# primary_cap_board_4s2p.net
KiCad netlist of a schematic drawn in EAGLE
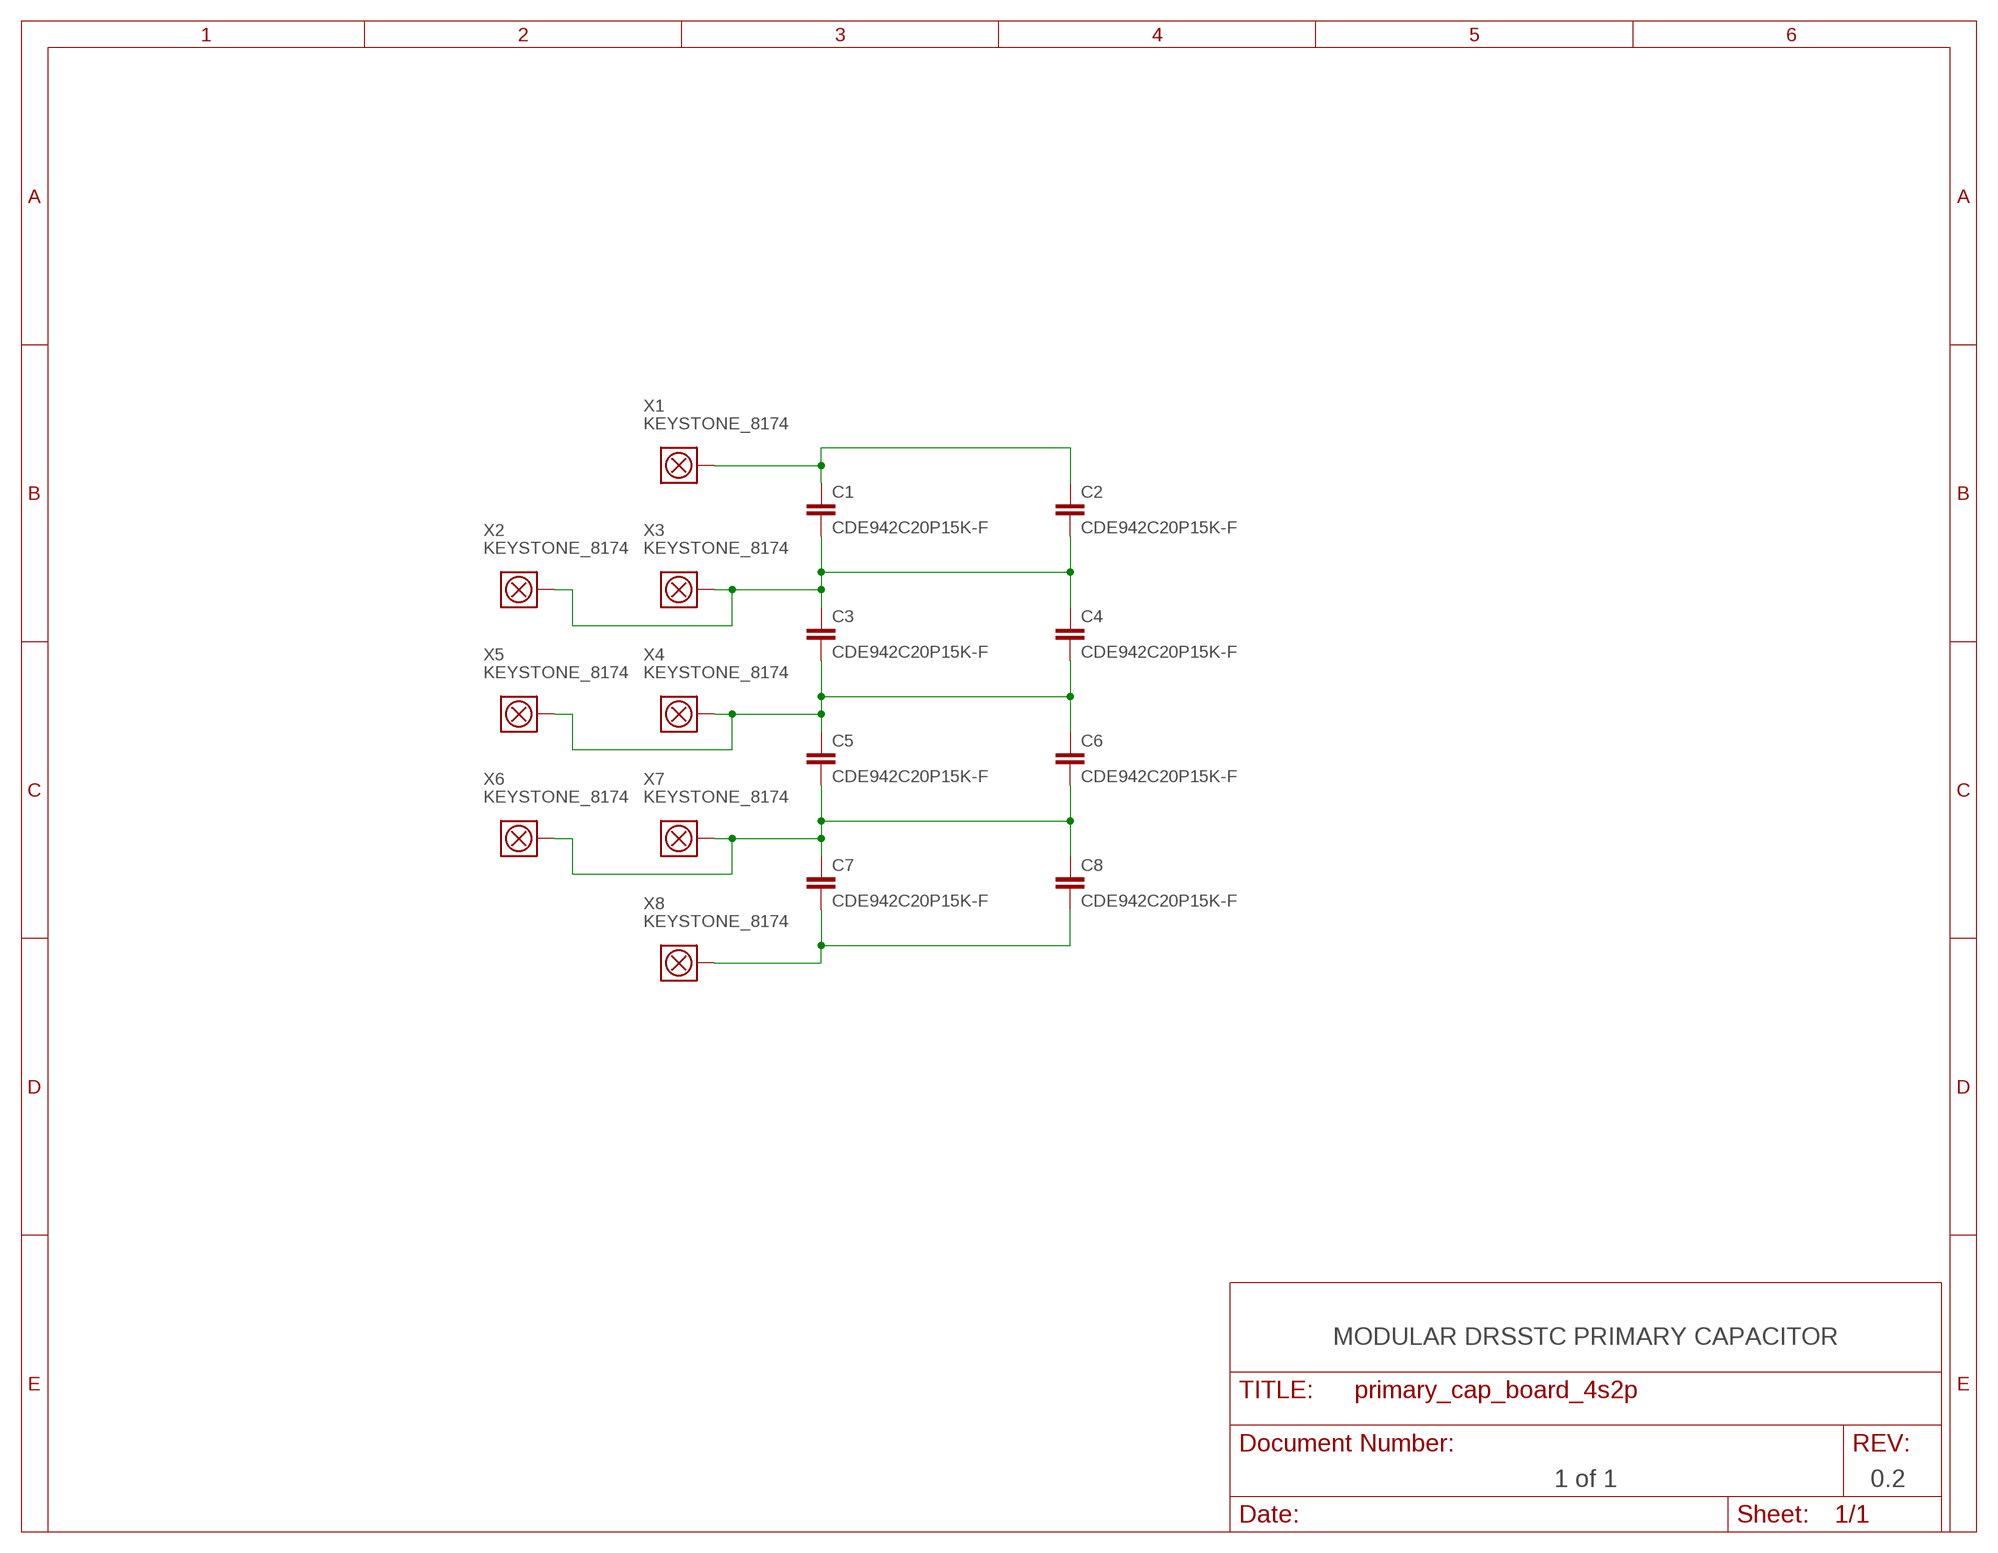
[diagram p0: schematic, sheet 1]

(export (version "E")
  (design (tool "Eeschema 10.0.6"))
  (components
    (comp (ref "C1")
      (value "CDE942C20P15K-F")
      (footprint "eagle-import:CDE942")
      (libsource (lib "eagle-import") (part "CDE942C20P15K-F"))
    )
    (comp (ref "C2")
      (value "CDE942C20P15K-F")
      (footprint "eagle-import:CDE942")
      (libsource (lib "eagle-import") (part "CDE942C20P15K-F"))
    )
    (comp (ref "C3")
      (value "CDE942C20P15K-F")
      (footprint "eagle-import:CDE942")
      (libsource (lib "eagle-import") (part "CDE942C20P15K-F"))
    )
    (comp (ref "C4")
      (value "CDE942C20P15K-F")
      (footprint "eagle-import:CDE942")
      (libsource (lib "eagle-import") (part "CDE942C20P15K-F"))
    )
    (comp (ref "C5")
      (value "CDE942C20P15K-F")
      (footprint "eagle-import:CDE942")
      (libsource (lib "eagle-import") (part "CDE942C20P15K-F"))
    )
    (comp (ref "C6")
      (value "CDE942C20P15K-F")
      (footprint "eagle-import:CDE942")
      (libsource (lib "eagle-import") (part "CDE942C20P15K-F"))
    )
    (comp (ref "C7")
      (value "CDE942C20P15K-F")
      (footprint "eagle-import:CDE942")
      (libsource (lib "eagle-import") (part "CDE942C20P15K-F"))
    )
    (comp (ref "C8")
      (value "CDE942C20P15K-F")
      (footprint "eagle-import:CDE942")
      (libsource (lib "eagle-import") (part "CDE942C20P15K-F"))
    )
    (comp (ref "X1")
      (value "KEYSTONE_8174")
      (footprint "eagle-import:CON_KEYSTONE_8174")
      (libsource (lib "eagle-import") (part "CON_KEYSTONE_8174"))
    )
    (comp (ref "X2")
      (value "KEYSTONE_8174")
      (footprint "eagle-import:CON_KEYSTONE_8174")
      (libsource (lib "eagle-import") (part "CON_KEYSTONE_8174"))
    )
    (comp (ref "X3")
      (value "KEYSTONE_8174")
      (footprint "eagle-import:CON_KEYSTONE_8174")
      (libsource (lib "eagle-import") (part "CON_KEYSTONE_8174"))
    )
    (comp (ref "X4")
      (value "KEYSTONE_8174")
      (footprint "eagle-import:CON_KEYSTONE_8174")
      (libsource (lib "eagle-import") (part "CON_KEYSTONE_8174"))
    )
    (comp (ref "X5")
      (value "KEYSTONE_8174")
      (footprint "eagle-import:CON_KEYSTONE_8174")
      (libsource (lib "eagle-import") (part "CON_KEYSTONE_8174"))
    )
    (comp (ref "X6")
      (value "KEYSTONE_8174")
      (footprint "eagle-import:CON_KEYSTONE_8174")
      (libsource (lib "eagle-import") (part "CON_KEYSTONE_8174"))
    )
    (comp (ref "X7")
      (value "KEYSTONE_8174")
      (footprint "eagle-import:CON_KEYSTONE_8174")
      (libsource (lib "eagle-import") (part "CON_KEYSTONE_8174"))
    )
    (comp (ref "X8")
      (value "KEYSTONE_8174")
      (footprint "eagle-import:CON_KEYSTONE_8174")
      (libsource (lib "eagle-import") (part "CON_KEYSTONE_8174"))
    )
  )
  (nets
    (net (code "1") (name "Net-(C1-1)") (class "Default")
      (node (ref "C1") (pin "P$1") (pinfunction "1_P$1") (pintype "passive"))
      (node (ref "C2") (pin "P$1") (pinfunction "1_P$1") (pintype "passive"))
      (node (ref "X1") (pin "P$1") (pinfunction "PIN1_P$1") (pintype "bidirectional"))
      (node (ref "X1") (pin "P$2") (pinfunction "PIN1_P$2") (pintype "bidirectional"))
      (node (ref "X1") (pin "P$3") (pinfunction "PIN1_P$3") (pintype "bidirectional"))
      (node (ref "X1") (pin "P$4") (pinfunction "PIN1_P$4") (pintype "bidirectional"))
    )
    (net (code "2") (name "Net-(C1-2)") (class "Default")
      (node (ref "C1") (pin "P$2") (pinfunction "2_P$2") (pintype "passive"))
      (node (ref "C2") (pin "P$2") (pinfunction "2_P$2") (pintype "passive"))
      (node (ref "C3") (pin "P$1") (pinfunction "1_P$1") (pintype "passive"))
      (node (ref "C4") (pin "P$1") (pinfunction "1_P$1") (pintype "passive"))
      (node (ref "X2") (pin "P$1") (pinfunction "PIN1_P$1") (pintype "bidirectional"))
      (node (ref "X2") (pin "P$2") (pinfunction "PIN1_P$2") (pintype "bidirectional"))
      (node (ref "X2") (pin "P$3") (pinfunction "PIN1_P$3") (pintype "bidirectional"))
      (node (ref "X2") (pin "P$4") (pinfunction "PIN1_P$4") (pintype "bidirectional"))
      (node (ref "X3") (pin "P$1") (pinfunction "PIN1_P$1") (pintype "bidirectional"))
      (node (ref "X3") (pin "P$2") (pinfunction "PIN1_P$2") (pintype "bidirectional"))
      (node (ref "X3") (pin "P$3") (pinfunction "PIN1_P$3") (pintype "bidirectional"))
      (node (ref "X3") (pin "P$4") (pinfunction "PIN1_P$4") (pintype "bidirectional"))
    )
    (net (code "3") (name "Net-(C3-2)") (class "Default")
      (node (ref "C3") (pin "P$2") (pinfunction "2_P$2") (pintype "passive"))
      (node (ref "C4") (pin "P$2") (pinfunction "2_P$2") (pintype "passive"))
      (node (ref "C5") (pin "P$1") (pinfunction "1_P$1") (pintype "passive"))
      (node (ref "C6") (pin "P$1") (pinfunction "1_P$1") (pintype "passive"))
      (node (ref "X4") (pin "P$1") (pinfunction "PIN1_P$1") (pintype "bidirectional"))
      (node (ref "X4") (pin "P$2") (pinfunction "PIN1_P$2") (pintype "bidirectional"))
      (node (ref "X4") (pin "P$3") (pinfunction "PIN1_P$3") (pintype "bidirectional"))
      (node (ref "X4") (pin "P$4") (pinfunction "PIN1_P$4") (pintype "bidirectional"))
      (node (ref "X5") (pin "P$1") (pinfunction "PIN1_P$1") (pintype "bidirectional"))
      (node (ref "X5") (pin "P$2") (pinfunction "PIN1_P$2") (pintype "bidirectional"))
      (node (ref "X5") (pin "P$3") (pinfunction "PIN1_P$3") (pintype "bidirectional"))
      (node (ref "X5") (pin "P$4") (pinfunction "PIN1_P$4") (pintype "bidirectional"))
    )
    (net (code "4") (name "Net-(C5-2)") (class "Default")
      (node (ref "C5") (pin "P$2") (pinfunction "2_P$2") (pintype "passive"))
      (node (ref "C6") (pin "P$2") (pinfunction "2_P$2") (pintype "passive"))
      (node (ref "C7") (pin "P$1") (pinfunction "1_P$1") (pintype "passive"))
      (node (ref "C8") (pin "P$1") (pinfunction "1_P$1") (pintype "passive"))
      (node (ref "X6") (pin "P$1") (pinfunction "PIN1_P$1") (pintype "bidirectional"))
      (node (ref "X6") (pin "P$2") (pinfunction "PIN1_P$2") (pintype "bidirectional"))
      (node (ref "X6") (pin "P$3") (pinfunction "PIN1_P$3") (pintype "bidirectional"))
      (node (ref "X6") (pin "P$4") (pinfunction "PIN1_P$4") (pintype "bidirectional"))
      (node (ref "X7") (pin "P$1") (pinfunction "PIN1_P$1") (pintype "bidirectional"))
      (node (ref "X7") (pin "P$2") (pinfunction "PIN1_P$2") (pintype "bidirectional"))
      (node (ref "X7") (pin "P$3") (pinfunction "PIN1_P$3") (pintype "bidirectional"))
      (node (ref "X7") (pin "P$4") (pinfunction "PIN1_P$4") (pintype "bidirectional"))
    )
    (net (code "5") (name "Net-(C7-2)") (class "Default")
      (node (ref "C7") (pin "P$2") (pinfunction "2_P$2") (pintype "passive"))
      (node (ref "C8") (pin "P$2") (pinfunction "2_P$2") (pintype "passive"))
      (node (ref "X8") (pin "P$1") (pinfunction "PIN1_P$1") (pintype "bidirectional"))
      (node (ref "X8") (pin "P$2") (pinfunction "PIN1_P$2") (pintype "bidirectional"))
      (node (ref "X8") (pin "P$3") (pinfunction "PIN1_P$3") (pintype "bidirectional"))
      (node (ref "X8") (pin "P$4") (pinfunction "PIN1_P$4") (pintype "bidirectional"))
    )
  )
)
